# proto.net
KiCad netlist of a schematic drawn in EAGLE
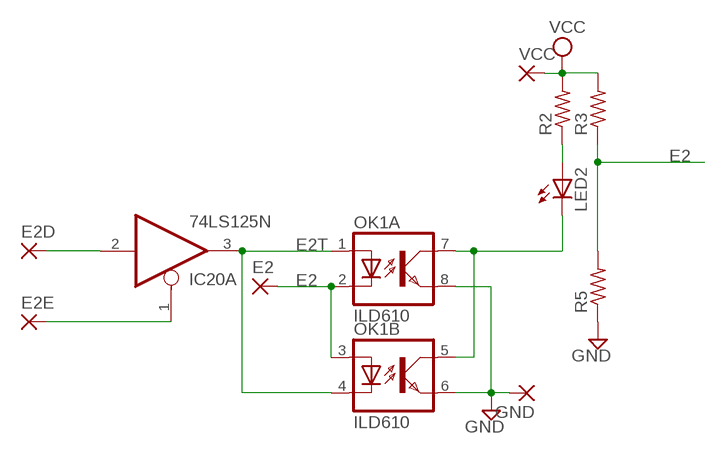
[diagram p0: schematic, sheet 1]

(export (version "E")
  (design (tool "Eeschema 10.0.6"))
  (components
    (comp (ref "E2")
      (value "1,6/0,9")
      (footprint "eagle-import:1,6_0,9")
      (libsource (lib "eagle-import") (part "1,6/0,9"))
    )
    (comp (ref "E2D")
      (value "1,6/0,9")
      (footprint "eagle-import:1,6_0,9")
      (libsource (lib "eagle-import") (part "1,6/0,9"))
    )
    (comp (ref "E2E")
      (value "1,6/0,9")
      (footprint "eagle-import:1,6_0,9")
      (libsource (lib "eagle-import") (part "1,6/0,9"))
    )
    (comp (ref "GND")
      (value "1,6/0,9")
      (footprint "eagle-import:1,6_0,9")
      (libsource (lib "eagle-import") (part "1,6/0,9"))
    )
    (comp (ref "IC20")
      (value "74LS125N")
      (footprint "eagle-import:DIL14")
      (libsource (lib "eagle-import") (part "74125NLS"))
    )
    (comp (ref "LED2")
      (value "LED5MM")
      (footprint "eagle-import:LED5MM")
      (libsource (lib "eagle-import") (part "LED5MM"))
    )
    (comp (ref "OK1")
      (value "ILD610")
      (footprint "eagle-import:DIL08")
      (fields (field (name "MF") "VISHAY/TELEFUNKEN") (field (name "MPN") "ILD610-4"))
      (libsource (lib "eagle-import") (part "ILD610"))
    )
    (comp (ref "R2")
      (value "R-US_0207/10")
      (footprint "eagle-import:0207_10")
      (libsource (lib "eagle-import") (part "R-US_0207/10"))
    )
    (comp (ref "R3")
      (value "R-US_0207/10")
      (footprint "eagle-import:0207_10")
      (libsource (lib "eagle-import") (part "R-US_0207/10"))
    )
    (comp (ref "R5")
      (value "R-US_0207/10")
      (footprint "eagle-import:0207_10")
      (libsource (lib "eagle-import") (part "R-US_0207/10"))
    )
    (comp (ref "VCC")
      (value "1,6/0,9")
      (footprint "eagle-import:1,6_0,9")
      (libsource (lib "eagle-import") (part "1,6/0,9"))
    )
  )
  (nets
    (net (code "1") (name "/E2") (class "Default")
      (node (ref "E2") (pin "1") (pinfunction "P_1") (pintype "passive"))
      (node (ref "OK1") (pin "2") (pinfunction "C_2") (pintype "passive"))
      (node (ref "OK1") (pin "3") (pinfunction "A_3") (pintype "passive"))
      (node (ref "R3") (pin "1") (pinfunction "1_1") (pintype "passive"))
      (node (ref "R5") (pin "2") (pinfunction "2_2") (pintype "passive"))
    )
    (net (code "2") (name "/E2T") (class "Default")
      (node (ref "IC20") (pin "3") (pinfunction "O_3") (pintype "tri_state"))
      (node (ref "OK1") (pin "1") (pinfunction "A_1") (pintype "passive"))
      (node (ref "OK1") (pin "4") (pinfunction "C_4") (pintype "passive"))
    )
    (net (code "3") (name "GND") (class "Default")
      (node (ref "GND") (pin "1") (pinfunction "P_1") (pintype "passive"))
      (node (ref "OK1") (pin "6") (pinfunction "EMIT_6") (pintype "passive"))
      (node (ref "OK1") (pin "8") (pinfunction "EMIT_8") (pintype "passive"))
      (node (ref "R5") (pin "1") (pinfunction "1_1") (pintype "passive"))
    )
    (net (code "4") (name "Net-(E2D-P)") (class "Default")
      (node (ref "E2D") (pin "1") (pinfunction "P_1") (pintype "passive"))
      (node (ref "IC20") (pin "2") (pinfunction "I_2") (pintype "input"))
    )
    (net (code "5") (name "Net-(E2E-P)") (class "Default")
      (node (ref "E2E") (pin "1") (pinfunction "P_1") (pintype "passive"))
      (node (ref "IC20") (pin "1") (pinfunction "OE_1") (pintype "input"))
    )
    (net (code "6") (name "Net-(LED2-C)") (class "Default")
      (node (ref "LED2") (pin "K") (pinfunction "C_K") (pintype "passive"))
      (node (ref "OK1") (pin "5") (pinfunction "COL_5") (pintype "passive"))
      (node (ref "OK1") (pin "7") (pinfunction "COL_7") (pintype "passive"))
    )
    (net (code "7") (name "Net-(LED2-PadA)") (class "Default")
      (node (ref "LED2") (pin "A") (pinfunction "A_A") (pintype "passive"))
      (node (ref "R2") (pin "1") (pinfunction "1_1") (pintype "passive"))
    )
    (net (code "8") (name "VCC") (class "Default")
      (node (ref "R2") (pin "2") (pinfunction "2_2") (pintype "passive"))
      (node (ref "R3") (pin "2") (pinfunction "2_2") (pintype "passive"))
      (node (ref "VCC") (pin "1") (pinfunction "P_1") (pintype "passive"))
    )
  )
)
